# rony_helloEcho.net
KiCad netlist of a schematic drawn in EAGLE
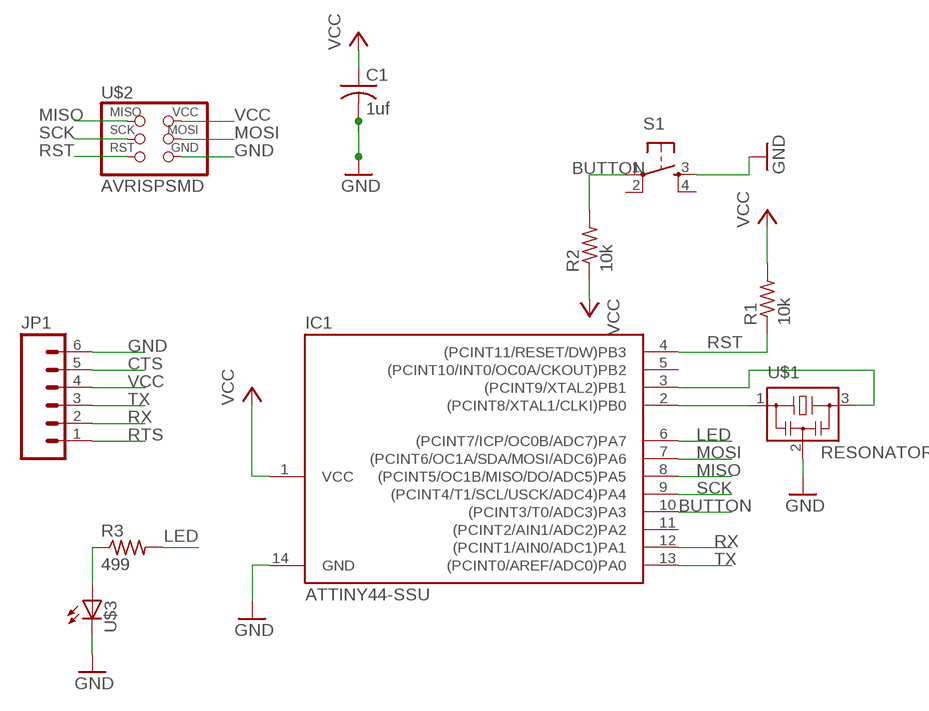
[diagram p0: schematic, sheet 1]

(export (version "E")
  (design (tool "Eeschema 10.0.6"))
  (components
    (comp (ref "C1")
      (value "1uf")
      (footprint "eagle-import:C1206")
      (libsource (lib "eagle-import") (part "C-USC1206"))
    )
    (comp (ref "IC1")
      (value "ATTINY44-SSU")
      (footprint "eagle-import:SOIC14")
      (libsource (lib "eagle-import") (part "ATTINY44-SSU"))
    )
    (comp (ref "JP1")
      (value "M06SMD")
      (footprint "eagle-import:1X06-SMD")
      (libsource (lib "eagle-import") (part "M06SMD"))
    )
    (comp (ref "R1")
      (value "10k")
      (footprint "eagle-import:R1206")
      (libsource (lib "eagle-import") (part "R-US_R1206"))
    )
    (comp (ref "R2")
      (value "10k")
      (footprint "eagle-import:R1206")
      (libsource (lib "eagle-import") (part "R-US_R1206"))
    )
    (comp (ref "R3")
      (value "499")
      (footprint "eagle-import:R1206FAB")
      (libsource (lib "eagle-import") (part "RES-US1206FAB"))
    )
    (comp (ref "S1")
      (value "6MM_SWITCH6MM_SWITCH")
      (footprint "eagle-import:6MM_SWITCH")
      (libsource (lib "eagle-import") (part "6MM_SWITCH6MM_SWITCH"))
    )
    (comp (ref "U$1")
      (value "RESONATOR")
      (footprint "eagle-import:EFOBM")
      (libsource (lib "eagle-import") (part "RESONATOR"))
    )
    (comp (ref "U$2")
      (value "AVRISPSMD")
      (footprint "eagle-import:2X03SMD")
      (libsource (lib "eagle-import") (part "AVRISPSMD"))
    )
    (comp (ref "U$3")
      (value "LED1206")
      (footprint "eagle-import:1206")
      (libsource (lib "eagle-import") (part "LED1206"))
    )
  )
  (nets
    (net (code "1") (name "/BUTTON") (class "Default")
      (node (ref "IC1") (pin "10") (pinfunction "(PCINT3/T0/ADC3)PA3_10") (pintype "bidirectional"))
      (node (ref "R2") (pin "2") (pinfunction "2_2") (pintype "passive"))
      (node (ref "S1") (pin "1") (pinfunction "P_1") (pintype "passive"))
    )
    (net (code "2") (name "/CTS") (class "Default")
      (node (ref "JP1") (pin "5") (pinfunction "5_5") (pintype "passive"))
    )
    (net (code "3") (name "/LED") (class "Default")
      (node (ref "IC1") (pin "6") (pinfunction "(PCINT7/ICP/OC0B/ADC7)PA7_6") (pintype "bidirectional"))
      (node (ref "R3") (pin "2") (pinfunction "2_2") (pintype "passive"))
    )
    (net (code "4") (name "/MISO") (class "Default")
      (node (ref "IC1") (pin "8") (pinfunction "(PCINT5/OC1B/MISO/DO/ADC5)PA5_8") (pintype "bidirectional"))
      (node (ref "U$2") (pin "1") (pinfunction "MISO_1") (pintype "passive"))
    )
    (net (code "5") (name "/MOSI") (class "Default")
      (node (ref "IC1") (pin "7") (pinfunction "(PCINT6/OC1A/SDA/MOSI/ADC6)PA6_7") (pintype "bidirectional"))
      (node (ref "U$2") (pin "4") (pinfunction "MOSI_4") (pintype "passive"))
    )
    (net (code "6") (name "/RST") (class "Default")
      (node (ref "IC1") (pin "4") (pinfunction "(PCINT11/RESET/DW)PB3_4") (pintype "bidirectional"))
      (node (ref "R1") (pin "1") (pinfunction "1_1") (pintype "passive"))
      (node (ref "U$2") (pin "5") (pinfunction "RST_5") (pintype "passive"))
    )
    (net (code "7") (name "/RTS") (class "Default")
      (node (ref "JP1") (pin "1") (pinfunction "1_1") (pintype "passive"))
    )
    (net (code "8") (name "/RX") (class "Default")
      (node (ref "IC1") (pin "12") (pinfunction "(PCINT1/AIN0/ADC1)PA1_12") (pintype "bidirectional"))
      (node (ref "JP1") (pin "2") (pinfunction "2_2") (pintype "passive"))
    )
    (net (code "9") (name "/SCK") (class "Default")
      (node (ref "IC1") (pin "9") (pinfunction "(PCINT4/T1/SCL/USCK/ADC4)PA4_9") (pintype "bidirectional"))
      (node (ref "U$2") (pin "3") (pinfunction "SCK_3") (pintype "passive"))
    )
    (net (code "10") (name "/TX") (class "Default")
      (node (ref "IC1") (pin "13") (pinfunction "(PCINT0/AREF/ADC0)PA0_13") (pintype "bidirectional"))
      (node (ref "JP1") (pin "3") (pinfunction "3_3") (pintype "passive"))
    )
    (net (code "11") (name "GND") (class "Default")
      (node (ref "C1") (pin "2") (pinfunction "2_2") (pintype "passive"))
      (node (ref "IC1") (pin "14") (pinfunction "GND_14") (pintype "power_in"))
      (node (ref "JP1") (pin "6") (pinfunction "6_6") (pintype "passive"))
      (node (ref "S1") (pin "3") (pinfunction "S_3") (pintype "passive"))
      (node (ref "U$1") (pin "2") (pinfunction "2_2") (pintype "passive"))
      (node (ref "U$2") (pin "6") (pinfunction "GND_6") (pintype "passive"))
      (node (ref "U$3") (pin "2") (pinfunction "C_2") (pintype "passive"))
    )
    (net (code "12") (name "Net-(IC1-(PCINT8{slash}XTAL1{slash}CLKI)PB0)") (class "Default")
      (node (ref "IC1") (pin "2") (pinfunction "(PCINT8/XTAL1/CLKI)PB0_2") (pintype "bidirectional"))
      (node (ref "U$1") (pin "1") (pinfunction "1_1") (pintype "passive"))
    )
    (net (code "13") (name "Net-(IC1-(PCINT9{slash}XTAL2)PB1)") (class "Default")
      (node (ref "IC1") (pin "3") (pinfunction "(PCINT9/XTAL2)PB1_3") (pintype "bidirectional"))
      (node (ref "U$1") (pin "3") (pinfunction "3_3") (pintype "passive"))
    )
    (net (code "14") (name "Net-(U$3-A)") (class "Default")
      (node (ref "R3") (pin "1") (pinfunction "1_1") (pintype "passive"))
      (node (ref "U$3") (pin "1") (pinfunction "A_1") (pintype "passive"))
    )
    (net (code "15") (name "VCC") (class "Default")
      (node (ref "C1") (pin "1") (pinfunction "1_1") (pintype "passive"))
      (node (ref "IC1") (pin "1") (pinfunction "VCC_1") (pintype "power_in"))
      (node (ref "JP1") (pin "4") (pinfunction "4_4") (pintype "passive"))
      (node (ref "R1") (pin "2") (pinfunction "2_2") (pintype "passive"))
      (node (ref "R2") (pin "1") (pinfunction "1_1") (pintype "passive"))
      (node (ref "U$2") (pin "2") (pinfunction "VCC_2") (pintype "passive"))
    )
    (net (code "16") (name "unconnected-(IC1-(PCINT2{slash}AIN1{slash}ADC2)PA2-Pad11)") (class "Default")
      (node (ref "IC1") (pin "11") (pinfunction "(PCINT2/AIN1/ADC2)PA2_11") (pintype "bidirectional"))
    )
    (net (code "17") (name "unconnected-(IC1-(PCINT10{slash}INT0{slash}OC0A{slash}CKOUT)PB2-Pad5)") (class "Default")
      (node (ref "IC1") (pin "5") (pinfunction "(PCINT10/INT0/OC0A/CKOUT)PB2_5") (pintype "bidirectional"))
    )
    (net (code "18") (name "unconnected-(S1-P1-Pad2)") (class "Default")
      (node (ref "S1") (pin "2") (pinfunction "P1_2") (pintype "passive"))
    )
    (net (code "19") (name "unconnected-(S1-S1-Pad4)") (class "Default")
      (node (ref "S1") (pin "4") (pinfunction "S1_4") (pintype "passive"))
    )
  )
)
